# ledmatrixdriver.net
KiCad netlist of a schematic drawn in EAGLE
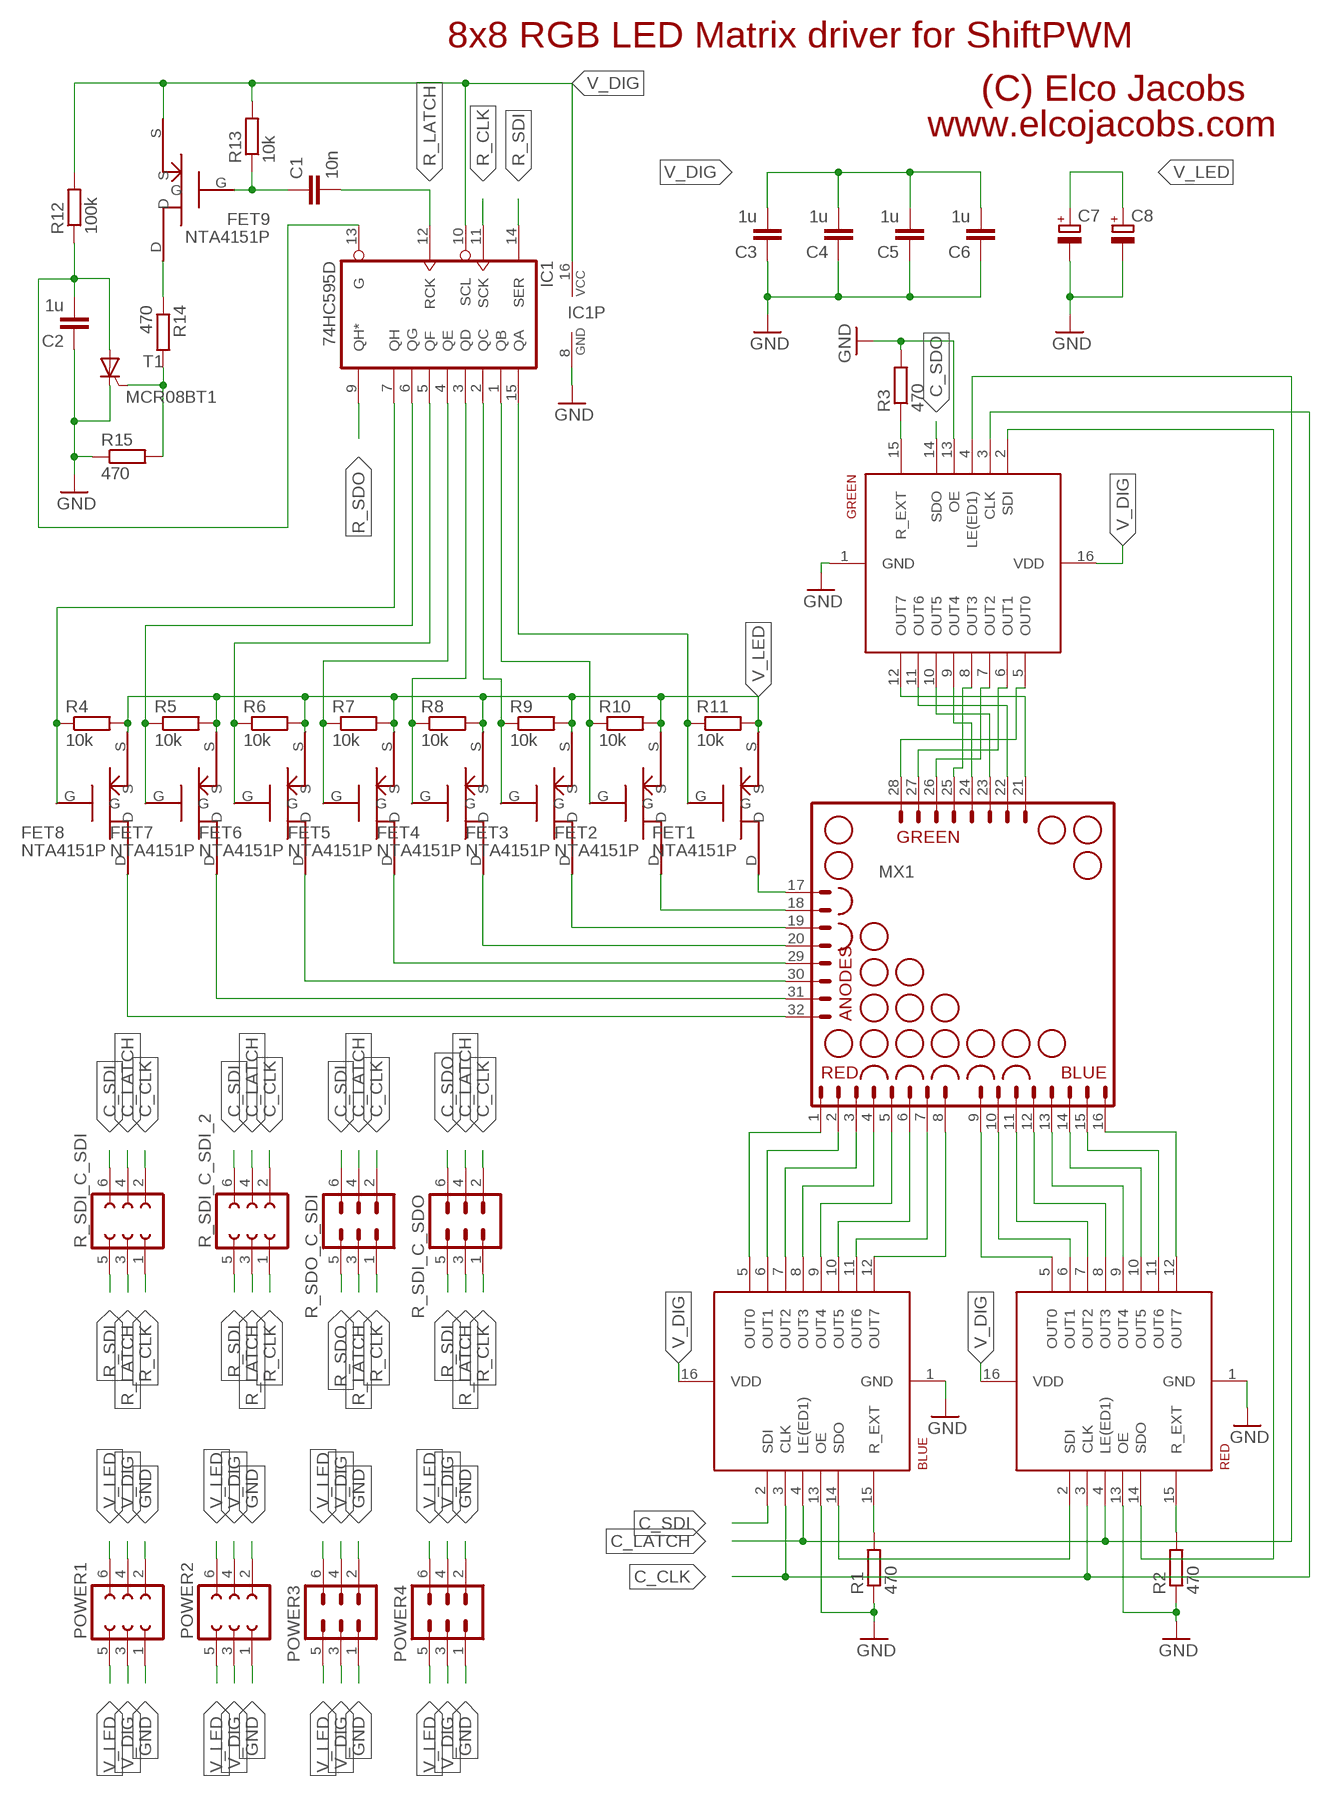
[diagram p0: schematic, sheet 1]

(export (version "E")
  (design (tool "Eeschema 10.0.6"))
  (components
    (comp (ref "BLUE")
      (value "TLC5916")
      (footprint "eagle-import:SOIC-16")
      (libsource (lib "eagle-import") (part "TLC5916/17"))
    )
    (comp (ref "C1")
      (value "10n")
      (footprint "eagle-import:C0805")
      (libsource (lib "eagle-import") (part "C-EUC0805"))
    )
    (comp (ref "C2")
      (value "1u")
      (footprint "eagle-import:C0805")
      (libsource (lib "eagle-import") (part "C-EUC0805"))
    )
    (comp (ref "C3")
      (value "1u")
      (footprint "eagle-import:C0805")
      (libsource (lib "eagle-import") (part "C-EUC0805"))
    )
    (comp (ref "C4")
      (value "1u")
      (footprint "eagle-import:C0805")
      (libsource (lib "eagle-import") (part "C-EUC0805"))
    )
    (comp (ref "C5")
      (value "1u")
      (footprint "eagle-import:C0805")
      (libsource (lib "eagle-import") (part "C-EUC0805"))
    )
    (comp (ref "C6")
      (value "1u")
      (footprint "eagle-import:C0805")
      (libsource (lib "eagle-import") (part "C-EUC0805"))
    )
    (comp (ref "C7")
      (value "CPOL-EU153CLV-0505")
      (footprint "eagle-import:153CLV-0505")
      (libsource (lib "eagle-import") (part "CPOL-EU153CLV-0505"))
    )
    (comp (ref "C8")
      (value "CPOL-EU153CLV-0505")
      (footprint "eagle-import:153CLV-0505")
      (libsource (lib "eagle-import") (part "CPOL-EU153CLV-0505"))
    )
    (comp (ref "FET1")
      (value "NTA4151P")
      (footprint "eagle-import:NTA4151P")
      (libsource (lib "eagle-import") (part "NTA4151P"))
    )
    (comp (ref "FET2")
      (value "NTA4151P")
      (footprint "eagle-import:NTA4151P")
      (libsource (lib "eagle-import") (part "NTA4151P"))
    )
    (comp (ref "FET3")
      (value "NTA4151P")
      (footprint "eagle-import:NTA4151P")
      (libsource (lib "eagle-import") (part "NTA4151P"))
    )
    (comp (ref "FET4")
      (value "NTA4151P")
      (footprint "eagle-import:NTA4151P")
      (libsource (lib "eagle-import") (part "NTA4151P"))
    )
    (comp (ref "FET5")
      (value "NTA4151P")
      (footprint "eagle-import:NTA4151P")
      (libsource (lib "eagle-import") (part "NTA4151P"))
    )
    (comp (ref "FET6")
      (value "NTA4151P")
      (footprint "eagle-import:NTA4151P")
      (libsource (lib "eagle-import") (part "NTA4151P"))
    )
    (comp (ref "FET7")
      (value "NTA4151P")
      (footprint "eagle-import:NTA4151P")
      (libsource (lib "eagle-import") (part "NTA4151P"))
    )
    (comp (ref "FET8")
      (value "NTA4151P")
      (footprint "eagle-import:NTA4151P")
      (libsource (lib "eagle-import") (part "NTA4151P"))
    )
    (comp (ref "FET9")
      (value "NTA4151P")
      (footprint "eagle-import:NTA4151P")
      (libsource (lib "eagle-import") (part "NTA4151P"))
    )
    (comp (ref "GREEN")
      (value "TLC5916")
      (footprint "eagle-import:SOIC-16")
      (libsource (lib "eagle-import") (part "TLC5916/17"))
    )
    (comp (ref "IC1")
      (value "74HC595D")
      (footprint "eagle-import:SO16")
      (libsource (lib "eagle-import") (part "74595DHC"))
    )
    (comp (ref "MX1")
      (value "MATRIX_8X8_TRICOLOR_ANODE_ROW")
      (footprint "eagle-import:MATRIX_60MM_32PIN")
      (libsource (lib "eagle-import") (part "MATRIX_8X8_TRICOLOR_ANODE_ROW"))
    )
    (comp (ref "POWER1")
      (value "FE03-2W")
      (footprint "eagle-import:FE03-2W")
      (libsource (lib "eagle-import") (part "FE03-2W"))
    )
    (comp (ref "POWER2")
      (value "FE03-2W")
      (footprint "eagle-import:FE03-2W")
      (libsource (lib "eagle-import") (part "FE03-2W"))
    )
    (comp (ref "POWER3")
      (value "MA03-2W")
      (footprint "eagle-import:MA03-2W")
      (libsource (lib "eagle-import") (part "MA03-2W"))
    )
    (comp (ref "POWER4")
      (value "MA03-2W")
      (footprint "eagle-import:MA03-2W")
      (libsource (lib "eagle-import") (part "MA03-2W"))
    )
    (comp (ref "R1")
      (value "470")
      (footprint "eagle-import:R0805")
      (libsource (lib "eagle-import") (part "R-EU_R0805"))
    )
    (comp (ref "R2")
      (value "470")
      (footprint "eagle-import:R0805")
      (libsource (lib "eagle-import") (part "R-EU_R0805"))
    )
    (comp (ref "R3")
      (value "470")
      (footprint "eagle-import:R0805")
      (libsource (lib "eagle-import") (part "R-EU_R0805"))
    )
    (comp (ref "R4")
      (value "10k")
      (footprint "eagle-import:R0402")
      (libsource (lib "eagle-import") (part "R-EU_R0402"))
    )
    (comp (ref "R5")
      (value "10k")
      (footprint "eagle-import:R0402")
      (libsource (lib "eagle-import") (part "R-EU_R0402"))
    )
    (comp (ref "R6")
      (value "10k")
      (footprint "eagle-import:R0402")
      (libsource (lib "eagle-import") (part "R-EU_R0402"))
    )
    (comp (ref "R7")
      (value "10k")
      (footprint "eagle-import:R0402")
      (libsource (lib "eagle-import") (part "R-EU_R0402"))
    )
    (comp (ref "R8")
      (value "10k")
      (footprint "eagle-import:R0402")
      (libsource (lib "eagle-import") (part "R-EU_R0402"))
    )
    (comp (ref "R9")
      (value "10k")
      (footprint "eagle-import:R0402")
      (libsource (lib "eagle-import") (part "R-EU_R0402"))
    )
    (comp (ref "R10")
      (value "10k")
      (footprint "eagle-import:R0402")
      (libsource (lib "eagle-import") (part "R-EU_R0402"))
    )
    (comp (ref "R11")
      (value "10k")
      (footprint "eagle-import:R0402")
      (libsource (lib "eagle-import") (part "R-EU_R0402"))
    )
    (comp (ref "R12")
      (value "100k")
      (footprint "eagle-import:R0805")
      (libsource (lib "eagle-import") (part "R-EU_R0805"))
    )
    (comp (ref "R13")
      (value "10k")
      (footprint "eagle-import:R0402")
      (libsource (lib "eagle-import") (part "R-EU_R0402"))
    )
    (comp (ref "R14")
      (value "470")
      (footprint "eagle-import:R0805")
      (libsource (lib "eagle-import") (part "R-EU_R0805"))
    )
    (comp (ref "R15")
      (value "470")
      (footprint "eagle-import:R0805")
      (libsource (lib "eagle-import") (part "R-EU_R0805"))
    )
    (comp (ref "RED")
      (value "TLC5916")
      (footprint "eagle-import:SOIC-16")
      (libsource (lib "eagle-import") (part "TLC5916/17"))
    )
    (comp (ref "R_SDI_C_SDI")
      (value "FE03-2W")
      (footprint "eagle-import:FE03-2W")
      (libsource (lib "eagle-import") (part "FE03-2W"))
    )
    (comp (ref "R_SDI_C_SDI_2")
      (value "FE03-2W")
      (footprint "eagle-import:FE03-2W")
      (libsource (lib "eagle-import") (part "FE03-2W"))
    )
    (comp (ref "R_SDI_C_SDO")
      (value "MA03-2W")
      (footprint "eagle-import:MA03-2W")
      (libsource (lib "eagle-import") (part "MA03-2W"))
    )
    (comp (ref "R_SDO_C_SDI")
      (value "MA03-2W")
      (footprint "eagle-import:MA03-2W")
      (libsource (lib "eagle-import") (part "MA03-2W"))
    )
    (comp (ref "T1")
      (value "MCR08BT1")
      (footprint "eagle-import:SOT223")
      (libsource (lib "eagle-import") (part "MCR08BT1"))
    )
  )
  (nets
    (net (code "1") (name "C_CLK") (class "Default")
      (node (ref "BLUE") (pin "3") (pinfunction "CLK_3") (pintype "bidirectional"))
      (node (ref "GREEN") (pin "3") (pinfunction "CLK_3") (pintype "bidirectional"))
      (node (ref "RED") (pin "3") (pinfunction "CLK_3") (pintype "bidirectional"))
      (node (ref "R_SDI_C_SDI") (pin "2") (pinfunction "2_2") (pintype "passive"))
      (node (ref "R_SDI_C_SDI_2") (pin "2") (pinfunction "2_2") (pintype "passive"))
      (node (ref "R_SDI_C_SDO") (pin "2") (pinfunction "2_2") (pintype "passive"))
      (node (ref "R_SDO_C_SDI") (pin "2") (pinfunction "2_2") (pintype "passive"))
    )
    (net (code "2") (name "C_LATCH") (class "Default")
      (node (ref "BLUE") (pin "4") (pinfunction "LE(ED1)_4") (pintype "bidirectional"))
      (node (ref "GREEN") (pin "4") (pinfunction "LE(ED1)_4") (pintype "bidirectional"))
      (node (ref "RED") (pin "4") (pinfunction "LE(ED1)_4") (pintype "bidirectional"))
      (node (ref "R_SDI_C_SDI") (pin "4") (pinfunction "4_4") (pintype "passive"))
      (node (ref "R_SDI_C_SDI_2") (pin "4") (pinfunction "4_4") (pintype "passive"))
      (node (ref "R_SDI_C_SDO") (pin "4") (pinfunction "4_4") (pintype "passive"))
      (node (ref "R_SDO_C_SDI") (pin "4") (pinfunction "4_4") (pintype "passive"))
    )
    (net (code "3") (name "C_SDI") (class "Default")
      (node (ref "BLUE") (pin "2") (pinfunction "SDI_2") (pintype "bidirectional"))
      (node (ref "R_SDI_C_SDI") (pin "6") (pinfunction "6_6") (pintype "passive"))
      (node (ref "R_SDI_C_SDI_2") (pin "6") (pinfunction "6_6") (pintype "passive"))
      (node (ref "R_SDO_C_SDI") (pin "6") (pinfunction "6_6") (pintype "passive"))
    )
    (net (code "4") (name "C_SDO") (class "Default")
      (node (ref "GREEN") (pin "14") (pinfunction "SDO_14") (pintype "bidirectional"))
      (node (ref "R_SDI_C_SDO") (pin "6") (pinfunction "6_6") (pintype "passive"))
    )
    (net (code "5") (name "GND") (class "Default")
      (node (ref "BLUE") (pin "1") (pinfunction "GND_1") (pintype "bidirectional"))
      (node (ref "BLUE") (pin "13") (pinfunction "OE_13") (pintype "bidirectional"))
      (node (ref "C2") (pin "1") (pinfunction "1_1") (pintype "passive"))
      (node (ref "C3") (pin "1") (pinfunction "1_1") (pintype "passive"))
      (node (ref "C4") (pin "1") (pinfunction "1_1") (pintype "passive"))
      (node (ref "C5") (pin "1") (pinfunction "1_1") (pintype "passive"))
      (node (ref "C6") (pin "1") (pinfunction "1_1") (pintype "passive"))
      (node (ref "C7") (pin "-") (pinfunction "-_-") (pintype "passive"))
      (node (ref "C8") (pin "-") (pinfunction "-_-") (pintype "passive"))
      (node (ref "GREEN") (pin "1") (pinfunction "GND_1") (pintype "bidirectional"))
      (node (ref "GREEN") (pin "13") (pinfunction "OE_13") (pintype "bidirectional"))
      (node (ref "IC1") (pin "8") (pinfunction "GND_8") (pintype "power_in"))
      (node (ref "POWER1") (pin "1") (pinfunction "1_1") (pintype "passive"))
      (node (ref "POWER1") (pin "2") (pinfunction "2_2") (pintype "passive"))
      (node (ref "POWER2") (pin "1") (pinfunction "1_1") (pintype "passive"))
      (node (ref "POWER2") (pin "2") (pinfunction "2_2") (pintype "passive"))
      (node (ref "POWER3") (pin "1") (pinfunction "1_1") (pintype "passive"))
      (node (ref "POWER3") (pin "2") (pinfunction "2_2") (pintype "passive"))
      (node (ref "POWER4") (pin "1") (pinfunction "1_1") (pintype "passive"))
      (node (ref "POWER4") (pin "2") (pinfunction "2_2") (pintype "passive"))
      (node (ref "R1") (pin "1") (pinfunction "1_1") (pintype "passive"))
      (node (ref "R15") (pin "1") (pinfunction "1_1") (pintype "passive"))
      (node (ref "R2") (pin "1") (pinfunction "1_1") (pintype "passive"))
      (node (ref "R3") (pin "2") (pinfunction "2_2") (pintype "passive"))
      (node (ref "RED") (pin "1") (pinfunction "GND_1") (pintype "bidirectional"))
      (node (ref "RED") (pin "13") (pinfunction "OE_13") (pintype "bidirectional"))
      (node (ref "T1") (pin "K") (pinfunction "C_K") (pintype "passive"))
    )
    (net (code "6") (name "Net-(BLUE-OUT0)") (class "Default")
      (node (ref "BLUE") (pin "5") (pinfunction "OUT0_5") (pintype "bidirectional"))
      (node (ref "MX1") (pin "1") (pinfunction "1_1") (pintype "passive"))
    )
    (net (code "7") (name "Net-(BLUE-OUT1)") (class "Default")
      (node (ref "BLUE") (pin "6") (pinfunction "OUT1_6") (pintype "bidirectional"))
      (node (ref "MX1") (pin "2") (pinfunction "2_2") (pintype "passive"))
    )
    (net (code "8") (name "Net-(BLUE-OUT2)") (class "Default")
      (node (ref "BLUE") (pin "7") (pinfunction "OUT2_7") (pintype "bidirectional"))
      (node (ref "MX1") (pin "3") (pinfunction "3_3") (pintype "passive"))
    )
    (net (code "9") (name "Net-(BLUE-OUT3)") (class "Default")
      (node (ref "BLUE") (pin "8") (pinfunction "OUT3_8") (pintype "bidirectional"))
      (node (ref "MX1") (pin "4") (pinfunction "4_4") (pintype "passive"))
    )
    (net (code "10") (name "Net-(BLUE-OUT4)") (class "Default")
      (node (ref "BLUE") (pin "9") (pinfunction "OUT4_9") (pintype "bidirectional"))
      (node (ref "MX1") (pin "5") (pinfunction "5_5") (pintype "passive"))
    )
    (net (code "11") (name "Net-(BLUE-OUT5)") (class "Default")
      (node (ref "BLUE") (pin "10") (pinfunction "OUT5_10") (pintype "bidirectional"))
      (node (ref "MX1") (pin "6") (pinfunction "6_6") (pintype "passive"))
    )
    (net (code "12") (name "Net-(BLUE-OUT6)") (class "Default")
      (node (ref "BLUE") (pin "11") (pinfunction "OUT6_11") (pintype "bidirectional"))
      (node (ref "MX1") (pin "7") (pinfunction "7_7") (pintype "passive"))
    )
    (net (code "13") (name "Net-(BLUE-OUT7)") (class "Default")
      (node (ref "BLUE") (pin "12") (pinfunction "OUT7_12") (pintype "bidirectional"))
      (node (ref "MX1") (pin "8") (pinfunction "8_8") (pintype "passive"))
    )
    (net (code "14") (name "Net-(BLUE-R_EXT)") (class "Default")
      (node (ref "BLUE") (pin "15") (pinfunction "R_EXT_15") (pintype "bidirectional"))
      (node (ref "R1") (pin "2") (pinfunction "2_2") (pintype "passive"))
    )
    (net (code "15") (name "Net-(BLUE-SDO)") (class "Default")
      (node (ref "BLUE") (pin "14") (pinfunction "SDO_14") (pintype "bidirectional"))
      (node (ref "RED") (pin "2") (pinfunction "SDI_2") (pintype "bidirectional"))
    )
    (net (code "16") (name "Net-(C1-Pad1)") (class "Default")
      (node (ref "C1") (pin "1") (pinfunction "1_1") (pintype "passive"))
      (node (ref "FET9") (pin "G") (pinfunction "G_G") (pintype "passive"))
      (node (ref "R13") (pin "1") (pinfunction "1_1") (pintype "passive"))
    )
    (net (code "17") (name "Net-(FET1-PadD)") (class "Default")
      (node (ref "FET1") (pin "D") (pinfunction "D_D") (pintype "passive"))
      (node (ref "MX1") (pin "17") (pinfunction "17_17") (pintype "passive"))
    )
    (net (code "18") (name "Net-(FET2-PadD)") (class "Default")
      (node (ref "FET2") (pin "D") (pinfunction "D_D") (pintype "passive"))
      (node (ref "MX1") (pin "18") (pinfunction "18_18") (pintype "passive"))
    )
    (net (code "19") (name "Net-(FET3-PadD)") (class "Default")
      (node (ref "FET3") (pin "D") (pinfunction "D_D") (pintype "passive"))
      (node (ref "MX1") (pin "19") (pinfunction "19_19") (pintype "passive"))
    )
    (net (code "20") (name "Net-(FET4-PadD)") (class "Default")
      (node (ref "FET4") (pin "D") (pinfunction "D_D") (pintype "passive"))
      (node (ref "MX1") (pin "20") (pinfunction "20_20") (pintype "passive"))
    )
    (net (code "21") (name "Net-(FET5-PadD)") (class "Default")
      (node (ref "FET5") (pin "D") (pinfunction "D_D") (pintype "passive"))
      (node (ref "MX1") (pin "29") (pinfunction "29_29") (pintype "passive"))
    )
    (net (code "22") (name "Net-(FET6-PadD)") (class "Default")
      (node (ref "FET6") (pin "D") (pinfunction "D_D") (pintype "passive"))
      (node (ref "MX1") (pin "30") (pinfunction "30_30") (pintype "passive"))
    )
    (net (code "23") (name "Net-(FET7-PadD)") (class "Default")
      (node (ref "FET7") (pin "D") (pinfunction "D_D") (pintype "passive"))
      (node (ref "MX1") (pin "31") (pinfunction "31_31") (pintype "passive"))
    )
    (net (code "24") (name "Net-(FET8-PadD)") (class "Default")
      (node (ref "FET8") (pin "D") (pinfunction "D_D") (pintype "passive"))
      (node (ref "MX1") (pin "32") (pinfunction "32_32") (pintype "passive"))
    )
    (net (code "25") (name "Net-(FET9-PadD)") (class "Default")
      (node (ref "FET9") (pin "D") (pinfunction "D_D") (pintype "passive"))
      (node (ref "R14") (pin "1") (pinfunction "1_1") (pintype "passive"))
    )
    (net (code "26") (name "Net-(GREEN-OUT0)") (class "Default")
      (node (ref "GREEN") (pin "5") (pinfunction "OUT0_5") (pintype "bidirectional"))
      (node (ref "MX1") (pin "28") (pinfunction "28_28") (pintype "passive"))
    )
    (net (code "27") (name "Net-(GREEN-OUT1)") (class "Default")
      (node (ref "GREEN") (pin "6") (pinfunction "OUT1_6") (pintype "bidirectional"))
      (node (ref "MX1") (pin "27") (pinfunction "27_27") (pintype "passive"))
    )
    (net (code "28") (name "Net-(GREEN-OUT2)") (class "Default")
      (node (ref "GREEN") (pin "7") (pinfunction "OUT2_7") (pintype "bidirectional"))
      (node (ref "MX1") (pin "26") (pinfunction "26_26") (pintype "passive"))
    )
    (net (code "29") (name "Net-(GREEN-OUT3)") (class "Default")
      (node (ref "GREEN") (pin "8") (pinfunction "OUT3_8") (pintype "bidirectional"))
      (node (ref "MX1") (pin "25") (pinfunction "25_25") (pintype "passive"))
    )
    (net (code "30") (name "Net-(GREEN-OUT4)") (class "Default")
      (node (ref "GREEN") (pin "9") (pinfunction "OUT4_9") (pintype "bidirectional"))
      (node (ref "MX1") (pin "24") (pinfunction "24_24") (pintype "passive"))
    )
    (net (code "31") (name "Net-(GREEN-OUT5)") (class "Default")
      (node (ref "GREEN") (pin "10") (pinfunction "OUT5_10") (pintype "bidirectional"))
      (node (ref "MX1") (pin "23") (pinfunction "23_23") (pintype "passive"))
    )
    (net (code "32") (name "Net-(GREEN-OUT6)") (class "Default")
      (node (ref "GREEN") (pin "11") (pinfunction "OUT6_11") (pintype "bidirectional"))
      (node (ref "MX1") (pin "22") (pinfunction "22_22") (pintype "passive"))
    )
    (net (code "33") (name "Net-(GREEN-OUT7)") (class "Default")
      (node (ref "GREEN") (pin "12") (pinfunction "OUT7_12") (pintype "bidirectional"))
      (node (ref "MX1") (pin "21") (pinfunction "21_21") (pintype "passive"))
    )
    (net (code "34") (name "Net-(GREEN-R_EXT)") (class "Default")
      (node (ref "GREEN") (pin "15") (pinfunction "R_EXT_15") (pintype "bidirectional"))
      (node (ref "R3") (pin "1") (pinfunction "1_1") (pintype "passive"))
    )
    (net (code "35") (name "Net-(GREEN-SDI)") (class "Default")
      (node (ref "GREEN") (pin "2") (pinfunction "SDI_2") (pintype "bidirectional"))
      (node (ref "RED") (pin "14") (pinfunction "SDO_14") (pintype "bidirectional"))
    )
    (net (code "36") (name "Net-(IC1A-G)") (class "Default")
      (node (ref "C2") (pin "2") (pinfunction "2_2") (pintype "passive"))
      (node (ref "IC1") (pin "13") (pinfunction "G_13") (pintype "input"))
      (node (ref "R12") (pin "1") (pinfunction "1_1") (pintype "passive"))
      (node (ref "T1") (pin "A") (pinfunction "A_A") (pintype "passive"))
      (node (ref "T1") (pin "A2") (pinfunction "A_A2") (pintype "passive"))
    )
    (net (code "37") (name "Net-(IC1A-QA)") (class "Default")
      (node (ref "FET1") (pin "G") (pinfunction "G_G") (pintype "passive"))
      (node (ref "IC1") (pin "15") (pinfunction "QA_15") (pintype "tri_state"))
      (node (ref "R11") (pin "1") (pinfunction "1_1") (pintype "passive"))
    )
    (net (code "38") (name "Net-(IC1A-QB)") (class "Default")
      (node (ref "FET2") (pin "G") (pinfunction "G_G") (pintype "passive"))
      (node (ref "IC1") (pin "1") (pinfunction "QB_1") (pintype "tri_state"))
      (node (ref "R10") (pin "1") (pinfunction "1_1") (pintype "passive"))
    )
    (net (code "39") (name "Net-(IC1A-QC)") (class "Default")
      (node (ref "FET3") (pin "G") (pinfunction "G_G") (pintype "passive"))
      (node (ref "IC1") (pin "2") (pinfunction "QC_2") (pintype "tri_state"))
      (node (ref "R9") (pin "1") (pinfunction "1_1") (pintype "passive"))
    )
    (net (code "40") (name "Net-(IC1A-QD)") (class "Default")
      (node (ref "FET4") (pin "G") (pinfunction "G_G") (pintype "passive"))
      (node (ref "IC1") (pin "3") (pinfunction "QD_3") (pintype "tri_state"))
      (node (ref "R8") (pin "1") (pinfunction "1_1") (pintype "passive"))
    )
    (net (code "41") (name "Net-(IC1A-QE)") (class "Default")
      (node (ref "FET5") (pin "G") (pinfunction "G_G") (pintype "passive"))
      (node (ref "IC1") (pin "4") (pinfunction "QE_4") (pintype "tri_state"))
      (node (ref "R7") (pin "1") (pinfunction "1_1") (pintype "passive"))
    )
    (net (code "42") (name "Net-(IC1A-QF)") (class "Default")
      (node (ref "FET6") (pin "G") (pinfunction "G_G") (pintype "passive"))
      (node (ref "IC1") (pin "5") (pinfunction "QF_5") (pintype "tri_state"))
      (node (ref "R6") (pin "1") (pinfunction "1_1") (pintype "passive"))
    )
    (net (code "43") (name "Net-(IC1A-QG)") (class "Default")
      (node (ref "FET7") (pin "G") (pinfunction "G_G") (pintype "passive"))
      (node (ref "IC1") (pin "6") (pinfunction "QG_6") (pintype "tri_state"))
      (node (ref "R5") (pin "1") (pinfunction "1_1") (pintype "passive"))
    )
    (net (code "44") (name "Net-(IC1A-QH)") (class "Default")
      (node (ref "FET8") (pin "G") (pinfunction "G_G") (pintype "passive"))
      (node (ref "IC1") (pin "7") (pinfunction "QH_7") (pintype "tri_state"))
      (node (ref "R4") (pin "1") (pinfunction "1_1") (pintype "passive"))
    )
    (net (code "45") (name "Net-(R14-Pad2)") (class "Default")
      (node (ref "R14") (pin "2") (pinfunction "2_2") (pintype "passive"))
      (node (ref "R15") (pin "2") (pinfunction "2_2") (pintype "passive"))
      (node (ref "T1") (pin "G") (pinfunction "G_G") (pintype "passive"))
    )
    (net (code "46") (name "Net-(RED-OUT0)") (class "Default")
      (node (ref "MX1") (pin "9") (pinfunction "9_9") (pintype "passive"))
      (node (ref "RED") (pin "5") (pinfunction "OUT0_5") (pintype "bidirectional"))
    )
    (net (code "47") (name "Net-(RED-OUT1)") (class "Default")
      (node (ref "MX1") (pin "10") (pinfunction "10_10") (pintype "passive"))
      (node (ref "RED") (pin "6") (pinfunction "OUT1_6") (pintype "bidirectional"))
    )
    (net (code "48") (name "Net-(RED-OUT2)") (class "Default")
      (node (ref "MX1") (pin "11") (pinfunction "11_11") (pintype "passive"))
      (node (ref "RED") (pin "7") (pinfunction "OUT2_7") (pintype "bidirectional"))
    )
    (net (code "49") (name "Net-(RED-OUT3)") (class "Default")
      (node (ref "MX1") (pin "12") (pinfunction "12_12") (pintype "passive"))
      (node (ref "RED") (pin "8") (pinfunction "OUT3_8") (pintype "bidirectional"))
    )
    (net (code "50") (name "Net-(RED-OUT4)") (class "Default")
      (node (ref "MX1") (pin "13") (pinfunction "13_13") (pintype "passive"))
      (node (ref "RED") (pin "9") (pinfunction "OUT4_9") (pintype "bidirectional"))
    )
    (net (code "51") (name "Net-(RED-OUT5)") (class "Default")
      (node (ref "MX1") (pin "14") (pinfunction "14_14") (pintype "passive"))
      (node (ref "RED") (pin "10") (pinfunction "OUT5_10") (pintype "bidirectional"))
    )
    (net (code "52") (name "Net-(RED-OUT6)") (class "Default")
      (node (ref "MX1") (pin "15") (pinfunction "15_15") (pintype "passive"))
      (node (ref "RED") (pin "11") (pinfunction "OUT6_11") (pintype "bidirectional"))
    )
    (net (code "53") (name "Net-(RED-OUT7)") (class "Default")
      (node (ref "MX1") (pin "16") (pinfunction "16_16") (pintype "passive"))
      (node (ref "RED") (pin "12") (pinfunction "OUT7_12") (pintype "bidirectional"))
    )
    (net (code "54") (name "Net-(RED-R_EXT)") (class "Default")
      (node (ref "R2") (pin "2") (pinfunction "2_2") (pintype "passive"))
      (node (ref "RED") (pin "15") (pinfunction "R_EXT_15") (pintype "bidirectional"))
    )
    (net (code "55") (name "R_CLK") (class "Default")
      (node (ref "IC1") (pin "11") (pinfunction "SCK_11") (pintype "input"))
      (node (ref "R_SDI_C_SDI") (pin "1") (pinfunction "1_1") (pintype "passive"))
      (node (ref "R_SDI_C_SDI_2") (pin "1") (pinfunction "1_1") (pintype "passive"))
      (node (ref "R_SDI_C_SDO") (pin "1") (pinfunction "1_1") (pintype "passive"))
      (node (ref "R_SDO_C_SDI") (pin "1") (pinfunction "1_1") (pintype "passive"))
    )
    (net (code "56") (name "R_LATCH") (class "Default")
      (node (ref "C1") (pin "2") (pinfunction "2_2") (pintype "passive"))
      (node (ref "IC1") (pin "12") (pinfunction "RCK_12") (pintype "input"))
      (node (ref "R_SDI_C_SDI") (pin "3") (pinfunction "3_3") (pintype "passive"))
      (node (ref "R_SDI_C_SDI_2") (pin "3") (pinfunction "3_3") (pintype "passive"))
      (node (ref "R_SDI_C_SDO") (pin "3") (pinfunction "3_3") (pintype "passive"))
      (node (ref "R_SDO_C_SDI") (pin "3") (pinfunction "3_3") (pintype "passive"))
    )
    (net (code "57") (name "R_SDI") (class "Default")
      (node (ref "IC1") (pin "14") (pinfunction "SER_14") (pintype "input"))
      (node (ref "R_SDI_C_SDI") (pin "5") (pinfunction "5_5") (pintype "passive"))
      (node (ref "R_SDI_C_SDI_2") (pin "5") (pinfunction "5_5") (pintype "passive"))
      (node (ref "R_SDI_C_SDO") (pin "5") (pinfunction "5_5") (pintype "passive"))
    )
    (net (code "58") (name "R_SDO") (class "Default")
      (node (ref "IC1") (pin "9") (pinfunction "QH*_9") (pintype "tri_state"))
      (node (ref "R_SDO_C_SDI") (pin "5") (pinfunction "5_5") (pintype "passive"))
    )
    (net (code "59") (name "V_DIG") (class "Default")
      (node (ref "BLUE") (pin "16") (pinfunction "VDD_16") (pintype "bidirectional"))
      (node (ref "C3") (pin "2") (pinfunction "2_2") (pintype "passive"))
      (node (ref "C4") (pin "2") (pinfunction "2_2") (pintype "passive"))
      (node (ref "C5") (pin "2") (pinfunction "2_2") (pintype "passive"))
      (node (ref "C6") (pin "2") (pinfunction "2_2") (pintype "passive"))
      (node (ref "FET9") (pin "S") (pinfunction "S_S") (pintype "passive"))
      (node (ref "GREEN") (pin "16") (pinfunction "VDD_16") (pintype "bidirectional"))
      (node (ref "IC1") (pin "10") (pinfunction "SCL_10") (pintype "input"))
      (node (ref "IC1") (pin "16") (pinfunction "VCC_16") (pintype "power_in"))
      (node (ref "POWER1") (pin "3") (pinfunction "3_3") (pintype "passive"))
      (node (ref "POWER1") (pin "4") (pinfunction "4_4") (pintype "passive"))
      (node (ref "POWER2") (pin "3") (pinfunction "3_3") (pintype "passive"))
      (node (ref "POWER2") (pin "4") (pinfunction "4_4") (pintype "passive"))
      (node (ref "POWER3") (pin "3") (pinfunction "3_3") (pintype "passive"))
      (node (ref "POWER3") (pin "4") (pinfunction "4_4") (pintype "passive"))
      (node (ref "POWER4") (pin "3") (pinfunction "3_3") (pintype "passive"))
      (node (ref "POWER4") (pin "4") (pinfunction "4_4") (pintype "passive"))
      (node (ref "R12") (pin "2") (pinfunction "2_2") (pintype "passive"))
      (node (ref "R13") (pin "2") (pinfunction "2_2") (pintype "passive"))
      (node (ref "RED") (pin "16") (pinfunction "VDD_16") (pintype "bidirectional"))
    )
    (net (code "60") (name "V_LED") (class "Default")
      (node (ref "C7") (pin "+") (pinfunction "+_+") (pintype "passive"))
      (node (ref "C8") (pin "+") (pinfunction "+_+") (pintype "passive"))
      (node (ref "FET1") (pin "S") (pinfunction "S_S") (pintype "passive"))
      (node (ref "FET2") (pin "S") (pinfunction "S_S") (pintype "passive"))
      (node (ref "FET3") (pin "S") (pinfunction "S_S") (pintype "passive"))
      (node (ref "FET4") (pin "S") (pinfunction "S_S") (pintype "passive"))
      (node (ref "FET5") (pin "S") (pinfunction "S_S") (pintype "passive"))
      (node (ref "FET6") (pin "S") (pinfunction "S_S") (pintype "passive"))
      (node (ref "FET7") (pin "S") (pinfunction "S_S") (pintype "passive"))
      (node (ref "FET8") (pin "S") (pinfunction "S_S") (pintype "passive"))
      (node (ref "POWER1") (pin "5") (pinfunction "5_5") (pintype "passive"))
      (node (ref "POWER1") (pin "6") (pinfunction "6_6") (pintype "passive"))
      (node (ref "POWER2") (pin "5") (pinfunction "5_5") (pintype "passive"))
      (node (ref "POWER2") (pin "6") (pinfunction "6_6") (pintype "passive"))
      (node (ref "POWER3") (pin "5") (pinfunction "5_5") (pintype "passive"))
      (node (ref "POWER3") (pin "6") (pinfunction "6_6") (pintype "passive"))
      (node (ref "POWER4") (pin "5") (pinfunction "5_5") (pintype "passive"))
      (node (ref "POWER4") (pin "6") (pinfunction "6_6") (pintype "passive"))
      (node (ref "R10") (pin "2") (pinfunction "2_2") (pintype "passive"))
      (node (ref "R11") (pin "2") (pinfunction "2_2") (pintype "passive"))
      (node (ref "R4") (pin "2") (pinfunction "2_2") (pintype "passive"))
      (node (ref "R5") (pin "2") (pinfunction "2_2") (pintype "passive"))
      (node (ref "R6") (pin "2") (pinfunction "2_2") (pintype "passive"))
      (node (ref "R7") (pin "2") (pinfunction "2_2") (pintype "passive"))
      (node (ref "R8") (pin "2") (pinfunction "2_2") (pintype "passive"))
      (node (ref "R9") (pin "2") (pinfunction "2_2") (pintype "passive"))
    )
  )
)
